# CONNECTEUR_1.net
KiCad netlist of a schematic drawn in Altium Designer
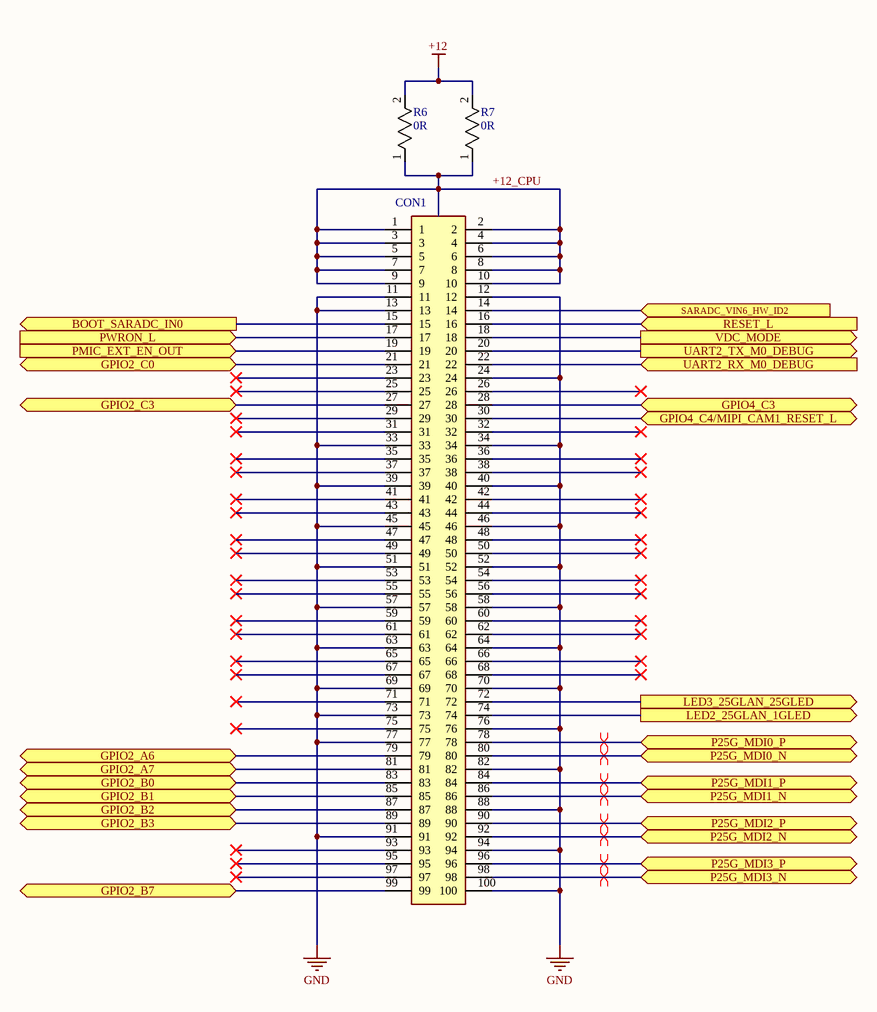
[diagram p0: CONNECTEUR_1.SchDoc]

(export (version "E")
  (design (tool "Eeschema 10.0.6"))
  (components
    (comp (ref "CON1")
      (value "DF40HC")
      (footprint "DF40HC30100DS04V51_MOD")
      (description "Stacking Board Connector, DF40 Series, Receptacle, 0.4 mm, 100, Surface Mount, G")
      (fields
        (field (name "MOUSER PART NUMBER") "798-DF40HC30100DS451")
        (field (name "ARROW PART NUMBER") "DF40HC(3.0)-100DS-0.4V(51")
      )
      (libsource (lib "DARKYDEN") (part "DF40HC(3.0)-100DS-0.4V(51)"))
    )
    (comp (ref "R6")
      (value "0R")
      (footprint "SamacSys:RESC1608X55N")
      (description "Zero Ohm Resistor, Jumper, 0603 [1608 Metric], Thick Film, 100 mW, 1 A, Surface Mount")
      (fields
        (field (name "MOUSER PART NUMBER") "667-ERJ-3GEY0R00V")
        (field (name "ARROW PART NUMBER") "ERJ-3GEY0R00V")
      )
      (libsource (lib "DARKYDEN") (part "ERJ-3GEY0R00V"))
    )
    (comp (ref "R7")
      (value "0R")
      (footprint "SamacSys:RESC1608X55N")
      (description "Zero Ohm Resistor, Jumper, 0603 [1608 Metric], Thick Film, 100 mW, 1 A, Surface Mount")
      (fields
        (field (name "MOUSER PART NUMBER") "667-ERJ-3GEY0R00V")
        (field (name "ARROW PART NUMBER") "ERJ-3GEY0R00V")
      )
      (libsource (lib "DARKYDEN") (part "ERJ-3GEY0R00V"))
    )
  )
  (nets
    (net (code "1") (name "+12") (class "Default")
      (node (ref "R6") (pin "2") (pinfunction "2_2") (pintype "passive"))
      (node (ref "R7") (pin "2") (pinfunction "2_2") (pintype "passive"))
    )
    (net (code "2") (name "/+12_CPU") (class "Default")
      (node (ref "CON1") (pin "1") (pinfunction "1_1") (pintype "passive"))
      (node (ref "CON1") (pin "10") (pinfunction "10_10") (pintype "passive"))
      (node (ref "CON1") (pin "2") (pinfunction "2_2") (pintype "passive"))
      (node (ref "CON1") (pin "3") (pinfunction "3_3") (pintype "passive"))
      (node (ref "CON1") (pin "4") (pinfunction "4_4") (pintype "passive"))
      (node (ref "CON1") (pin "5") (pinfunction "5_5") (pintype "passive"))
      (node (ref "CON1") (pin "6") (pinfunction "6_6") (pintype "passive"))
      (node (ref "CON1") (pin "7") (pinfunction "7_7") (pintype "passive"))
      (node (ref "CON1") (pin "8") (pinfunction "8_8") (pintype "passive"))
      (node (ref "CON1") (pin "9") (pinfunction "9_9") (pintype "passive"))
      (node (ref "R6") (pin "1") (pinfunction "1_1") (pintype "passive"))
      (node (ref "R7") (pin "1") (pinfunction "1_1") (pintype "passive"))
    )
    (net (code "3") (name "/BOOT_SARADC_IN0") (class "Default")
      (node (ref "CON1") (pin "15") (pinfunction "15_15") (pintype "passive"))
    )
    (net (code "4") (name "/GPIO2_A6") (class "Default")
      (node (ref "CON1") (pin "79") (pinfunction "79_79") (pintype "passive"))
    )
    (net (code "5") (name "/GPIO2_A7") (class "Default")
      (node (ref "CON1") (pin "81") (pinfunction "81_81") (pintype "passive"))
    )
    (net (code "6") (name "/GPIO2_B0") (class "Default")
      (node (ref "CON1") (pin "83") (pinfunction "83_83") (pintype "passive"))
    )
    (net (code "7") (name "/GPIO2_B1") (class "Default")
      (node (ref "CON1") (pin "85") (pinfunction "85_85") (pintype "passive"))
    )
    (net (code "8") (name "/GPIO2_B2") (class "Default")
      (node (ref "CON1") (pin "87") (pinfunction "87_87") (pintype "passive"))
    )
    (net (code "9") (name "/GPIO2_B3") (class "Default")
      (node (ref "CON1") (pin "89") (pinfunction "89_89") (pintype "passive"))
    )
    (net (code "10") (name "/GPIO2_B7") (class "Default")
      (node (ref "CON1") (pin "99") (pinfunction "99_99") (pintype "passive"))
    )
    (net (code "11") (name "/GPIO2_C0") (class "Default")
      (node (ref "CON1") (pin "21") (pinfunction "21_21") (pintype "passive"))
    )
    (net (code "12") (name "/GPIO2_C3") (class "Default")
      (node (ref "CON1") (pin "27") (pinfunction "27_27") (pintype "passive"))
    )
    (net (code "13") (name "/GPIO4_C3") (class "Default")
      (node (ref "CON1") (pin "28") (pinfunction "28_28") (pintype "passive"))
    )
    (net (code "14") (name "/GPIO4_C4{slash}MIPI_CAM1_RESET_L") (class "Default")
      (node (ref "CON1") (pin "30") (pinfunction "30_30") (pintype "passive"))
    )
    (net (code "15") (name "/LED2_25GLAN_1GLED") (class "Default")
      (node (ref "CON1") (pin "74") (pinfunction "74_74") (pintype "passive"))
    )
    (net (code "16") (name "/LED3_25GLAN_25GLED") (class "Default")
      (node (ref "CON1") (pin "72") (pinfunction "72_72") (pintype "passive"))
    )
    (net (code "17") (name "/P25G_MDI0_N") (class "Default")
      (node (ref "CON1") (pin "80") (pinfunction "80_80") (pintype "passive"))
    )
    (net (code "18") (name "/P25G_MDI0_P") (class "Default")
      (node (ref "CON1") (pin "78") (pinfunction "78_78") (pintype "passive"))
    )
    (net (code "19") (name "/P25G_MDI1_N") (class "Default")
      (node (ref "CON1") (pin "86") (pinfunction "86_86") (pintype "passive"))
    )
    (net (code "20") (name "/P25G_MDI1_P") (class "Default")
      (node (ref "CON1") (pin "84") (pinfunction "84_84") (pintype "passive"))
    )
    (net (code "21") (name "/P25G_MDI2_N") (class "Default")
      (node (ref "CON1") (pin "92") (pinfunction "92_92") (pintype "passive"))
    )
    (net (code "22") (name "/P25G_MDI2_P") (class "Default")
      (node (ref "CON1") (pin "90") (pinfunction "90_90") (pintype "passive"))
    )
    (net (code "23") (name "/P25G_MDI3_N") (class "Default")
      (node (ref "CON1") (pin "98") (pinfunction "98_98") (pintype "passive"))
    )
    (net (code "24") (name "/P25G_MDI3_P") (class "Default")
      (node (ref "CON1") (pin "96") (pinfunction "96_96") (pintype "passive"))
    )
    (net (code "25") (name "/PMIC_EXT_EN_OUT") (class "Default")
      (node (ref "CON1") (pin "19") (pinfunction "19_19") (pintype "passive"))
    )
    (net (code "26") (name "/PWRON_L") (class "Default")
      (node (ref "CON1") (pin "17") (pinfunction "17_17") (pintype "passive"))
    )
    (net (code "27") (name "/RESET_L") (class "Default")
      (node (ref "CON1") (pin "16") (pinfunction "16_16") (pintype "passive"))
    )
    (net (code "28") (name "/SARADC_VIN6_HW_ID2") (class "Default")
      (node (ref "CON1") (pin "14") (pinfunction "14_14") (pintype "passive"))
    )
    (net (code "29") (name "/UART2_RX_M0_DEBUG") (class "Default")
      (node (ref "CON1") (pin "22") (pinfunction "22_22") (pintype "passive"))
    )
    (net (code "30") (name "/UART2_TX_M0_DEBUG") (class "Default")
      (node (ref "CON1") (pin "20") (pinfunction "20_20") (pintype "passive"))
    )
    (net (code "31") (name "/VDC_MODE") (class "Default")
      (node (ref "CON1") (pin "18") (pinfunction "18_18") (pintype "passive"))
    )
    (net (code "32") (name "GND") (class "Default")
      (node (ref "CON1") (pin "100") (pinfunction "100_100") (pintype "passive"))
      (node (ref "CON1") (pin "11") (pinfunction "11_11") (pintype "passive"))
      (node (ref "CON1") (pin "12") (pinfunction "12_12") (pintype "passive"))
      (node (ref "CON1") (pin "13") (pinfunction "13_13") (pintype "passive"))
      (node (ref "CON1") (pin "24") (pinfunction "24_24") (pintype "passive"))
      (node (ref "CON1") (pin "33") (pinfunction "33_33") (pintype "passive"))
      (node (ref "CON1") (pin "34") (pinfunction "34_34") (pintype "passive"))
      (node (ref "CON1") (pin "39") (pinfunction "39_39") (pintype "passive"))
      (node (ref "CON1") (pin "40") (pinfunction "40_40") (pintype "passive"))
      (node (ref "CON1") (pin "45") (pinfunction "45_45") (pintype "passive"))
      (node (ref "CON1") (pin "46") (pinfunction "46_46") (pintype "passive"))
      (node (ref "CON1") (pin "51") (pinfunction "51_51") (pintype "passive"))
      (node (ref "CON1") (pin "52") (pinfunction "52_52") (pintype "passive"))
      (node (ref "CON1") (pin "57") (pinfunction "57_57") (pintype "passive"))
      (node (ref "CON1") (pin "58") (pinfunction "58_58") (pintype "passive"))
      (node (ref "CON1") (pin "63") (pinfunction "63_63") (pintype "passive"))
      (node (ref "CON1") (pin "64") (pinfunction "64_64") (pintype "passive"))
      (node (ref "CON1") (pin "69") (pinfunction "69_69") (pintype "passive"))
      (node (ref "CON1") (pin "70") (pinfunction "70_70") (pintype "passive"))
      (node (ref "CON1") (pin "73") (pinfunction "73_73") (pintype "passive"))
      (node (ref "CON1") (pin "76") (pinfunction "76_76") (pintype "passive"))
      (node (ref "CON1") (pin "77") (pinfunction "77_77") (pintype "passive"))
      (node (ref "CON1") (pin "82") (pinfunction "82_82") (pintype "passive"))
      (node (ref "CON1") (pin "88") (pinfunction "88_88") (pintype "passive"))
      (node (ref "CON1") (pin "91") (pinfunction "91_91") (pintype "passive"))
      (node (ref "CON1") (pin "94") (pinfunction "94_94") (pintype "passive"))
    )
    (net (code "33") (name "unconnected-(CON1-Pad23)") (class "Default")
      (node (ref "CON1") (pin "23") (pinfunction "23_23") (pintype "passive+no_connect"))
    )
    (net (code "34") (name "unconnected-(CON1-Pad25)") (class "Default")
      (node (ref "CON1") (pin "25") (pinfunction "25_25") (pintype "passive+no_connect"))
    )
    (net (code "35") (name "unconnected-(CON1-Pad26)") (class "Default")
      (node (ref "CON1") (pin "26") (pinfunction "26_26") (pintype "passive+no_connect"))
    )
    (net (code "36") (name "unconnected-(CON1-Pad29)") (class "Default")
      (node (ref "CON1") (pin "29") (pinfunction "29_29") (pintype "passive+no_connect"))
    )
    (net (code "37") (name "unconnected-(CON1-Pad31)") (class "Default")
      (node (ref "CON1") (pin "31") (pinfunction "31_31") (pintype "passive+no_connect"))
    )
    (net (code "38") (name "unconnected-(CON1-Pad32)") (class "Default")
      (node (ref "CON1") (pin "32") (pinfunction "32_32") (pintype "passive+no_connect"))
    )
    (net (code "39") (name "unconnected-(CON1-Pad35)") (class "Default")
      (node (ref "CON1") (pin "35") (pinfunction "35_35") (pintype "passive+no_connect"))
    )
    (net (code "40") (name "unconnected-(CON1-Pad36)") (class "Default")
      (node (ref "CON1") (pin "36") (pinfunction "36_36") (pintype "passive+no_connect"))
    )
    (net (code "41") (name "unconnected-(CON1-Pad37)") (class "Default")
      (node (ref "CON1") (pin "37") (pinfunction "37_37") (pintype "passive+no_connect"))
    )
    (net (code "42") (name "unconnected-(CON1-Pad38)") (class "Default")
      (node (ref "CON1") (pin "38") (pinfunction "38_38") (pintype "passive+no_connect"))
    )
    (net (code "43") (name "unconnected-(CON1-Pad41)") (class "Default")
      (node (ref "CON1") (pin "41") (pinfunction "41_41") (pintype "passive+no_connect"))
    )
    (net (code "44") (name "unconnected-(CON1-Pad42)") (class "Default")
      (node (ref "CON1") (pin "42") (pinfunction "42_42") (pintype "passive+no_connect"))
    )
    (net (code "45") (name "unconnected-(CON1-Pad43)") (class "Default")
      (node (ref "CON1") (pin "43") (pinfunction "43_43") (pintype "passive+no_connect"))
    )
    (net (code "46") (name "unconnected-(CON1-Pad44)") (class "Default")
      (node (ref "CON1") (pin "44") (pinfunction "44_44") (pintype "passive+no_connect"))
    )
    (net (code "47") (name "unconnected-(CON1-Pad47)") (class "Default")
      (node (ref "CON1") (pin "47") (pinfunction "47_47") (pintype "passive+no_connect"))
    )
    (net (code "48") (name "unconnected-(CON1-Pad48)") (class "Default")
      (node (ref "CON1") (pin "48") (pinfunction "48_48") (pintype "passive+no_connect"))
    )
    (net (code "49") (name "unconnected-(CON1-Pad49)") (class "Default")
      (node (ref "CON1") (pin "49") (pinfunction "49_49") (pintype "passive+no_connect"))
    )
    (net (code "50") (name "unconnected-(CON1-Pad50)") (class "Default")
      (node (ref "CON1") (pin "50") (pinfunction "50_50") (pintype "passive+no_connect"))
    )
    (net (code "51") (name "unconnected-(CON1-Pad53)") (class "Default")
      (node (ref "CON1") (pin "53") (pinfunction "53_53") (pintype "passive+no_connect"))
    )
    (net (code "52") (name "unconnected-(CON1-Pad54)") (class "Default")
      (node (ref "CON1") (pin "54") (pinfunction "54_54") (pintype "passive+no_connect"))
    )
    (net (code "53") (name "unconnected-(CON1-Pad55)") (class "Default")
      (node (ref "CON1") (pin "55") (pinfunction "55_55") (pintype "passive+no_connect"))
    )
    (net (code "54") (name "unconnected-(CON1-Pad56)") (class "Default")
      (node (ref "CON1") (pin "56") (pinfunction "56_56") (pintype "passive+no_connect"))
    )
    (net (code "55") (name "unconnected-(CON1-Pad59)") (class "Default")
      (node (ref "CON1") (pin "59") (pinfunction "59_59") (pintype "passive+no_connect"))
    )
    (net (code "56") (name "unconnected-(CON1-Pad60)") (class "Default")
      (node (ref "CON1") (pin "60") (pinfunction "60_60") (pintype "passive+no_connect"))
    )
    (net (code "57") (name "unconnected-(CON1-Pad61)") (class "Default")
      (node (ref "CON1") (pin "61") (pinfunction "61_61") (pintype "passive+no_connect"))
    )
    (net (code "58") (name "unconnected-(CON1-Pad62)") (class "Default")
      (node (ref "CON1") (pin "62") (pinfunction "62_62") (pintype "passive+no_connect"))
    )
    (net (code "59") (name "unconnected-(CON1-Pad65)") (class "Default")
      (node (ref "CON1") (pin "65") (pinfunction "65_65") (pintype "passive+no_connect"))
    )
    (net (code "60") (name "unconnected-(CON1-Pad66)") (class "Default")
      (node (ref "CON1") (pin "66") (pinfunction "66_66") (pintype "passive+no_connect"))
    )
    (net (code "61") (name "unconnected-(CON1-Pad67)") (class "Default")
      (node (ref "CON1") (pin "67") (pinfunction "67_67") (pintype "passive+no_connect"))
    )
    (net (code "62") (name "unconnected-(CON1-Pad68)") (class "Default")
      (node (ref "CON1") (pin "68") (pinfunction "68_68") (pintype "passive+no_connect"))
    )
    (net (code "63") (name "unconnected-(CON1-Pad71)") (class "Default")
      (node (ref "CON1") (pin "71") (pinfunction "71_71") (pintype "passive+no_connect"))
    )
    (net (code "64") (name "unconnected-(CON1-Pad75)") (class "Default")
      (node (ref "CON1") (pin "75") (pinfunction "75_75") (pintype "passive+no_connect"))
    )
    (net (code "65") (name "unconnected-(CON1-Pad93)") (class "Default")
      (node (ref "CON1") (pin "93") (pinfunction "93_93") (pintype "passive+no_connect"))
    )
    (net (code "66") (name "unconnected-(CON1-Pad95)") (class "Default")
      (node (ref "CON1") (pin "95") (pinfunction "95_95") (pintype "passive+no_connect"))
    )
    (net (code "67") (name "unconnected-(CON1-Pad97)") (class "Default")
      (node (ref "CON1") (pin "97") (pinfunction "97_97") (pintype "passive+no_connect"))
    )
  )
)
